# Raspberry_main.net
KiCad netlist of a schematic drawn in Altium Designer
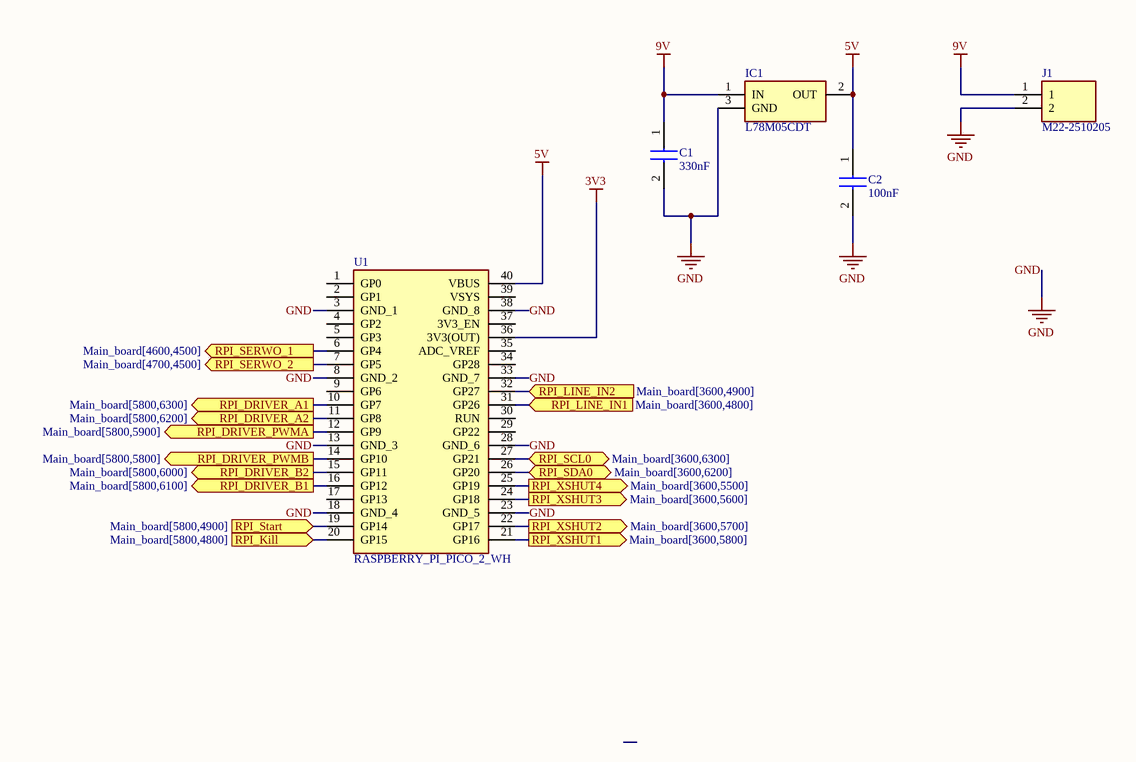
[diagram p0: Raspberry_main.SchDoc]

(export (version "E")
  (design (tool "Eeschema 10.0.6"))
  (components
    (comp (ref "C1")
      (value "330nF")
      (footprint "SamacSys:CAPC1608X87N")
      (description "Capacitor")
      (fields (field (name "MANUFACTURER_PART_NUMBER") "0603X334K250CT"))
      (libsource (lib "*") (part "0603X334K250CT"))
    )
    (comp (ref "C2")
      (value "100nF")
      (footprint "SamacSys:CAPC1608X90N")
      (description "Capacitor")
      (fields
        (field (name "MANUFACTURER_PART_NUMBER") "06031C104MAT2A")
        (field (name "MOUSER PART NUMBER") "581-06031C104MAT2A")
      )
      (libsource (lib "*") (part "06031C104MAT2A"))
    )
    (comp (ref "IC1")
      (value "L78M05CDT")
      (footprint "SamacSys:TO225P972X240-3N")
      (description "Integrated Circuit")
      (fields (field (name "MOUSER PART NUMBER") "511-L78M05CDT"))
      (libsource (lib "*") (part "L78M05CDT"))
    )
    (comp (ref "J1")
      (value "M22-2510205")
      (footprint "PCB 2 pin pads")
      (description "Connector")
      (fields (field (name "MOUSER PART NUMBER") "855-M22-2510205"))
      (libsource (lib "SamacSys") (part "M22-2510205"))
    )
    (comp (ref "U1")
      (value "RASPBERRY_PI_PICO_2_WH")
      (footprint "SamacSys:RASPBERRYPIPICO2WH")
      (description "Undefined or Miscellaneous")
      (fields (field (name "MANUFACTURER_PART_NUMBER") "RASPBERRY PI PICO 2 WH"))
      (libsource (lib "SamacSys") (part "RASPBERRY_PI_PICO_2_WH"))
    )
  )
  (nets
    (net (code "1") (name "/RPI_DRIVER_A1") (class "Default")
      (node (ref "U1") (pin "10") (pinfunction "GP7_10") (pintype "passive"))
    )
    (net (code "2") (name "/RPI_DRIVER_A2") (class "Default")
      (node (ref "U1") (pin "11") (pinfunction "GP8_11") (pintype "passive"))
    )
    (net (code "3") (name "/RPI_DRIVER_B1") (class "Default")
      (node (ref "U1") (pin "16") (pinfunction "GP12_16") (pintype "passive"))
    )
    (net (code "4") (name "/RPI_DRIVER_B2") (class "Default")
      (node (ref "U1") (pin "15") (pinfunction "GP11_15") (pintype "passive"))
    )
    (net (code "5") (name "/RPI_DRIVER_PWMA") (class "Default")
      (node (ref "U1") (pin "12") (pinfunction "GP9_12") (pintype "passive"))
    )
    (net (code "6") (name "/RPI_DRIVER_PWMB") (class "Default")
      (node (ref "U1") (pin "14") (pinfunction "GP10_14") (pintype "passive"))
    )
    (net (code "7") (name "/RPI_Kill") (class "Default")
      (node (ref "U1") (pin "20") (pinfunction "GP15_20") (pintype "passive"))
    )
    (net (code "8") (name "/RPI_LINE_IN1") (class "Default")
      (node (ref "U1") (pin "31") (pinfunction "GP26_31") (pintype "passive"))
    )
    (net (code "9") (name "/RPI_LINE_IN2") (class "Default")
      (node (ref "U1") (pin "32") (pinfunction "GP27_32") (pintype "passive"))
    )
    (net (code "10") (name "/RPI_SCL0") (class "Default")
      (node (ref "U1") (pin "27") (pinfunction "GP21_27") (pintype "passive"))
    )
    (net (code "11") (name "/RPI_SDA0") (class "Default")
      (node (ref "U1") (pin "26") (pinfunction "GP20_26") (pintype "passive"))
    )
    (net (code "12") (name "/RPI_SERWO_1") (class "Default")
      (node (ref "U1") (pin "6") (pinfunction "GP4_6") (pintype "passive"))
    )
    (net (code "13") (name "/RPI_SERWO_2") (class "Default")
      (node (ref "U1") (pin "7") (pinfunction "GP5_7") (pintype "passive"))
    )
    (net (code "14") (name "/RPI_Start") (class "Default")
      (node (ref "U1") (pin "19") (pinfunction "GP14_19") (pintype "passive"))
    )
    (net (code "15") (name "/RPI_XSHUT1") (class "Default")
      (node (ref "U1") (pin "21") (pinfunction "GP16_21") (pintype "passive"))
    )
    (net (code "16") (name "/RPI_XSHUT2") (class "Default")
      (node (ref "U1") (pin "22") (pinfunction "GP17_22") (pintype "passive"))
    )
    (net (code "17") (name "/RPI_XSHUT3") (class "Default")
      (node (ref "U1") (pin "24") (pinfunction "GP18_24") (pintype "passive"))
    )
    (net (code "18") (name "/RPI_XSHUT4") (class "Default")
      (node (ref "U1") (pin "25") (pinfunction "GP19_25") (pintype "passive"))
    )
    (net (code "19") (name "3V3") (class "Default")
      (node (ref "U1") (pin "36") (pinfunction "3V3(OUT)_36") (pintype "passive"))
    )
    (net (code "20") (name "5V") (class "Default")
      (node (ref "C2") (pin "1") (pinfunction "1_1") (pintype "passive"))
      (node (ref "IC1") (pin "2") (pinfunction "OUT_2") (pintype "passive"))
      (node (ref "U1") (pin "40") (pinfunction "VBUS_40") (pintype "passive"))
    )
    (net (code "21") (name "9V") (class "Default")
      (node (ref "C1") (pin "1") (pinfunction "1_1") (pintype "passive"))
      (node (ref "IC1") (pin "1") (pinfunction "IN_1") (pintype "passive"))
      (node (ref "J1") (pin "1") (pinfunction "1_1") (pintype "passive"))
    )
    (net (code "22") (name "GND") (class "Default")
      (node (ref "C1") (pin "2") (pinfunction "2_2") (pintype "passive"))
      (node (ref "C2") (pin "2") (pinfunction "2_2") (pintype "passive"))
      (node (ref "IC1") (pin "3") (pinfunction "GND_3") (pintype "passive"))
      (node (ref "J1") (pin "2") (pinfunction "2_2") (pintype "passive"))
      (node (ref "U1") (pin "13") (pinfunction "GND_3_13") (pintype "passive"))
      (node (ref "U1") (pin "18") (pinfunction "GND_4_18") (pintype "passive"))
      (node (ref "U1") (pin "23") (pinfunction "GND_5_23") (pintype "passive"))
      (node (ref "U1") (pin "28") (pinfunction "GND_6_28") (pintype "passive"))
      (node (ref "U1") (pin "3") (pinfunction "GND_1_3") (pintype "passive"))
      (node (ref "U1") (pin "33") (pinfunction "GND_7_33") (pintype "passive"))
      (node (ref "U1") (pin "38") (pinfunction "GND_8_38") (pintype "passive"))
      (node (ref "U1") (pin "8") (pinfunction "GND_2_8") (pintype "passive"))
    )
    (net (code "23") (name "unconnected-(U1-3V3_EN-Pad37)") (class "Default")
      (node (ref "U1") (pin "37") (pinfunction "3V3_EN_37") (pintype "passive"))
    )
    (net (code "24") (name "unconnected-(U1-ADC_VREF-Pad35)") (class "Default")
      (node (ref "U1") (pin "35") (pinfunction "ADC_VREF_35") (pintype "passive"))
    )
    (net (code "25") (name "unconnected-(U1-GP0-Pad1)") (class "Default")
      (node (ref "U1") (pin "1") (pinfunction "GP0_1") (pintype "passive"))
    )
    (net (code "26") (name "unconnected-(U1-GP1-Pad2)") (class "Default")
      (node (ref "U1") (pin "2") (pinfunction "GP1_2") (pintype "passive"))
    )
    (net (code "27") (name "unconnected-(U1-GP2-Pad4)") (class "Default")
      (node (ref "U1") (pin "4") (pinfunction "GP2_4") (pintype "passive"))
    )
    (net (code "28") (name "unconnected-(U1-GP3-Pad5)") (class "Default")
      (node (ref "U1") (pin "5") (pinfunction "GP3_5") (pintype "passive"))
    )
    (net (code "29") (name "unconnected-(U1-GP6-Pad9)") (class "Default")
      (node (ref "U1") (pin "9") (pinfunction "GP6_9") (pintype "passive"))
    )
    (net (code "30") (name "unconnected-(U1-GP13-Pad17)") (class "Default")
      (node (ref "U1") (pin "17") (pinfunction "GP13_17") (pintype "passive"))
    )
    (net (code "31") (name "unconnected-(U1-GP22-Pad29)") (class "Default")
      (node (ref "U1") (pin "29") (pinfunction "GP22_29") (pintype "passive"))
    )
    (net (code "32") (name "unconnected-(U1-GP28-Pad34)") (class "Default")
      (node (ref "U1") (pin "34") (pinfunction "GP28_34") (pintype "passive"))
    )
    (net (code "33") (name "unconnected-(U1-RUN-Pad30)") (class "Default")
      (node (ref "U1") (pin "30") (pinfunction "RUN_30") (pintype "passive"))
    )
    (net (code "34") (name "unconnected-(U1-VSYS-Pad39)") (class "Default")
      (node (ref "U1") (pin "39") (pinfunction "VSYS_39") (pintype "passive"))
    )
  )
)
